# schematic.net
KiCad netlist of a schematic drawn in EasyEDA
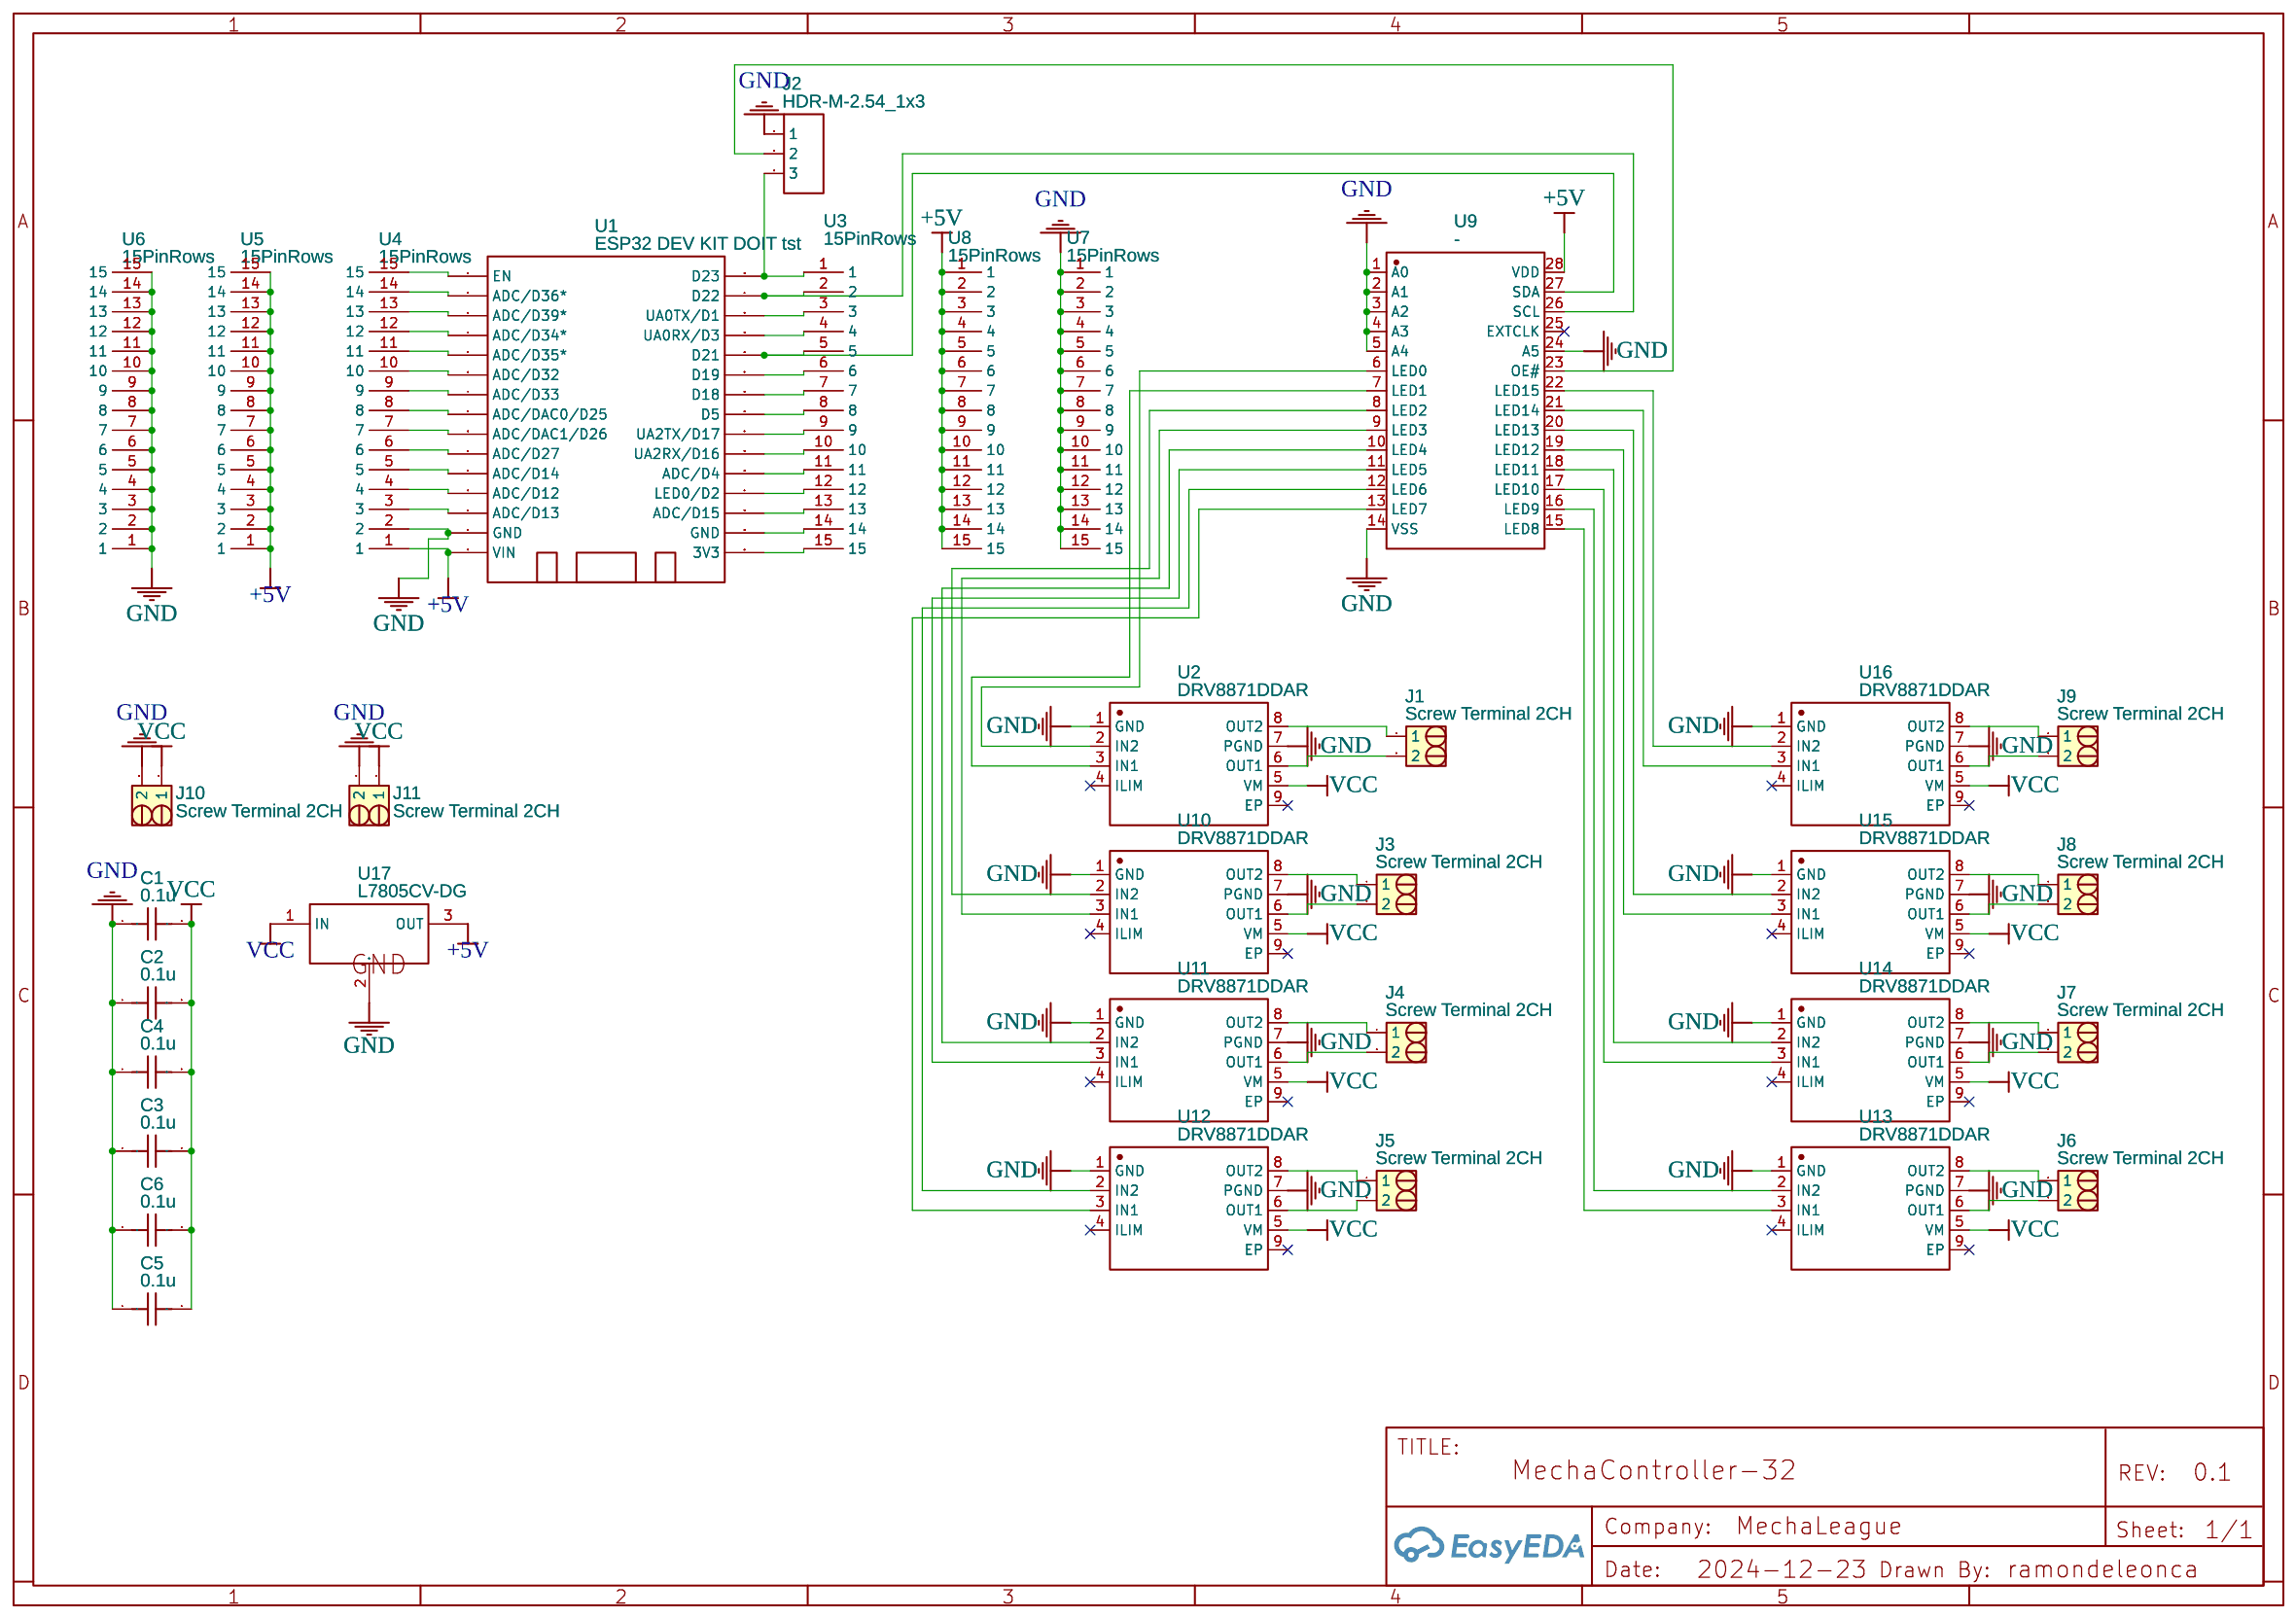
[diagram p0: schematic sheet]

(export (version "E")
  (design (tool "Eeschema 10.0.6"))
  (components
    (comp (ref "C1") (value "0.1u") (libsource (lib "") (part "C_0603_US")))
    (comp (ref "C2") (value "0.1u") (libsource (lib "") (part "C_0603_US")))
    (comp (ref "C3") (value "0.1u") (libsource (lib "") (part "C_0603_US")))
    (comp (ref "C4") (value "0.1u") (libsource (lib "") (part "C_0603_US")))
    (comp (ref "C5") (value "0.1u") (libsource (lib "") (part "C_0603_US")))
    (comp (ref "C6") (value "0.1u") (libsource (lib "") (part "C_0603_US")))
    (comp (ref "J1") (value "Screw Terminal 2CH") (libsource (lib "") (part "Screw Terminal 2CH")))
    (comp (ref "J2") (value "HDR-M-2.54_1x3") (libsource (lib "") (part "HDR-M-2.54_1x3")))
    (comp (ref "J3") (value "Screw Terminal 2CH") (libsource (lib "") (part "Screw Terminal 2CH")))
    (comp (ref "J4") (value "Screw Terminal 2CH") (libsource (lib "") (part "Screw Terminal 2CH")))
    (comp (ref "J5") (value "Screw Terminal 2CH") (libsource (lib "") (part "Screw Terminal 2CH")))
    (comp (ref "J6") (value "Screw Terminal 2CH") (libsource (lib "") (part "Screw Terminal 2CH")))
    (comp (ref "J7") (value "Screw Terminal 2CH") (libsource (lib "") (part "Screw Terminal 2CH")))
    (comp (ref "J8") (value "Screw Terminal 2CH") (libsource (lib "") (part "Screw Terminal 2CH")))
    (comp (ref "J9") (value "Screw Terminal 2CH") (libsource (lib "") (part "Screw Terminal 2CH")))
    (comp (ref "J10") (value "Screw Terminal 2CH") (libsource (lib "") (part "Screw Terminal 2CH_1")))
    (comp (ref "J11") (value "Screw Terminal 2CH") (libsource (lib "") (part "Screw Terminal 2CH_1")))
    (comp (ref "U1") (value "ESP32 DEV KIT DOIT tst") (libsource (lib "") (part "ESP32 DEV KIT DOIT tst")))
    (comp (ref "U2")
      (value "DRV8871DDAR")
      (fields (field (name "Manufacturer") "TI(德州仪器)"))
      (libsource (lib "") (part "DRV8871DDAR"))
    )
    (comp (ref "U3") (value "15PinRows") (libsource (lib "") (part "15PinRows_1")))
    (comp (ref "U4") (value "15PinRows") (libsource (lib "") (part "15PinRows")))
    (comp (ref "U5") (value "15PinRows") (libsource (lib "") (part "15PinRows")))
    (comp (ref "U6") (value "15PinRows") (libsource (lib "") (part "15PinRows")))
    (comp (ref "U7") (value "15PinRows") (libsource (lib "") (part "15PinRows_1")))
    (comp (ref "U8") (value "15PinRows") (libsource (lib "") (part "15PinRows_1")))
    (comp (ref "U9")
      (value "-")
      (fields (field (name "Manufacturer Part") "PCA9685PW,118") (field (name "Manufacturer") "NXP(恩智浦)"))
      (libsource (lib "") (part "PCA9685PW,118"))
    )
    (comp (ref "U10")
      (value "DRV8871DDAR")
      (fields (field (name "Manufacturer") "TI(德州仪器)"))
      (libsource (lib "") (part "DRV8871DDAR"))
    )
    (comp (ref "U11")
      (value "DRV8871DDAR")
      (fields (field (name "Manufacturer") "TI(德州仪器)"))
      (libsource (lib "") (part "DRV8871DDAR"))
    )
    (comp (ref "U12")
      (value "DRV8871DDAR")
      (fields (field (name "Manufacturer") "TI(德州仪器)"))
      (libsource (lib "") (part "DRV8871DDAR"))
    )
    (comp (ref "U13")
      (value "DRV8871DDAR")
      (fields (field (name "Manufacturer") "TI(德州仪器)"))
      (libsource (lib "") (part "DRV8871DDAR"))
    )
    (comp (ref "U14")
      (value "DRV8871DDAR")
      (fields (field (name "Manufacturer") "TI(德州仪器)"))
      (libsource (lib "") (part "DRV8871DDAR"))
    )
    (comp (ref "U15")
      (value "DRV8871DDAR")
      (fields (field (name "Manufacturer") "TI(德州仪器)"))
      (libsource (lib "") (part "DRV8871DDAR"))
    )
    (comp (ref "U16")
      (value "DRV8871DDAR")
      (fields (field (name "Manufacturer") "TI(德州仪器)"))
      (libsource (lib "") (part "DRV8871DDAR"))
    )
    (comp (ref "U17")
      (value "L7805CV-DG")
      (fields (field (name "Manufacturer") "ST(意法半导体)"))
      (libsource (lib "") (part "L7805CV-DG"))
    )
  )
  (nets
    (net (code "1") (name "+5V") (class "Default")
      (node (ref "U1") (pin "15") (pinfunction "VIN_15") (pintype "input"))
      (node (ref "U17") (pin "3") (pinfunction "OUT_3") (pintype "passive"))
      (node (ref "U4") (pin "1") (pinfunction "1_1") (pintype "unspecified"))
      (node (ref "U5") (pin "1") (pinfunction "1_1") (pintype "unspecified"))
      (node (ref "U5") (pin "10") (pinfunction "10_10") (pintype "unspecified"))
      (node (ref "U5") (pin "11") (pinfunction "11_11") (pintype "unspecified"))
      (node (ref "U5") (pin "12") (pinfunction "12_12") (pintype "unspecified"))
      (node (ref "U5") (pin "13") (pinfunction "13_13") (pintype "unspecified"))
      (node (ref "U5") (pin "14") (pinfunction "14_14") (pintype "unspecified"))
      (node (ref "U5") (pin "15") (pinfunction "15_15") (pintype "unspecified"))
      (node (ref "U5") (pin "2") (pinfunction "2_2") (pintype "unspecified"))
      (node (ref "U5") (pin "3") (pinfunction "3_3") (pintype "unspecified"))
      (node (ref "U5") (pin "4") (pinfunction "4_4") (pintype "unspecified"))
      (node (ref "U5") (pin "5") (pinfunction "5_5") (pintype "unspecified"))
      (node (ref "U5") (pin "6") (pinfunction "6_6") (pintype "unspecified"))
      (node (ref "U5") (pin "7") (pinfunction "7_7") (pintype "unspecified"))
      (node (ref "U5") (pin "8") (pinfunction "8_8") (pintype "unspecified"))
      (node (ref "U5") (pin "9") (pinfunction "9_9") (pintype "unspecified"))
      (node (ref "U8") (pin "1") (pinfunction "1_1") (pintype "unspecified"))
      (node (ref "U8") (pin "10") (pinfunction "10_10") (pintype "unspecified"))
      (node (ref "U8") (pin "11") (pinfunction "11_11") (pintype "unspecified"))
      (node (ref "U8") (pin "12") (pinfunction "12_12") (pintype "unspecified"))
      (node (ref "U8") (pin "13") (pinfunction "13_13") (pintype "unspecified"))
      (node (ref "U8") (pin "14") (pinfunction "14_14") (pintype "unspecified"))
      (node (ref "U8") (pin "15") (pinfunction "15_15") (pintype "unspecified"))
      (node (ref "U8") (pin "2") (pinfunction "2_2") (pintype "unspecified"))
      (node (ref "U8") (pin "3") (pinfunction "3_3") (pintype "unspecified"))
      (node (ref "U8") (pin "4") (pinfunction "4_4") (pintype "unspecified"))
      (node (ref "U8") (pin "5") (pinfunction "5_5") (pintype "unspecified"))
      (node (ref "U8") (pin "6") (pinfunction "6_6") (pintype "unspecified"))
      (node (ref "U8") (pin "7") (pinfunction "7_7") (pintype "unspecified"))
      (node (ref "U8") (pin "8") (pinfunction "8_8") (pintype "unspecified"))
      (node (ref "U8") (pin "9") (pinfunction "9_9") (pintype "unspecified"))
      (node (ref "U9") (pin "28") (pinfunction "VDD_28") (pintype "unspecified"))
    )
    (net (code "2") (name "GND") (class "Default")
      (node (ref "C1") (pin "1") (pinfunction "1_1") (pintype "unspecified"))
      (node (ref "C2") (pin "1") (pinfunction "1_1") (pintype "unspecified"))
      (node (ref "C3") (pin "1") (pinfunction "1_1") (pintype "unspecified"))
      (node (ref "C4") (pin "1") (pinfunction "1_1") (pintype "unspecified"))
      (node (ref "C5") (pin "1") (pinfunction "1_1") (pintype "unspecified"))
      (node (ref "C6") (pin "1") (pinfunction "1_1") (pintype "unspecified"))
      (node (ref "J10") (pin "2") (pinfunction "2_2") (pintype "unspecified"))
      (node (ref "J11") (pin "2") (pinfunction "2_2") (pintype "unspecified"))
      (node (ref "J2") (pin "1") (pinfunction "1_1") (pintype "input"))
      (node (ref "U1") (pin "14") (pinfunction "GND_14") (pintype "bidirectional"))
      (node (ref "U10") (pin "1") (pinfunction "GND_1") (pintype "unspecified"))
      (node (ref "U10") (pin "7") (pinfunction "PGND_7") (pintype "unspecified"))
      (node (ref "U11") (pin "1") (pinfunction "GND_1") (pintype "unspecified"))
      (node (ref "U11") (pin "7") (pinfunction "PGND_7") (pintype "unspecified"))
      (node (ref "U12") (pin "1") (pinfunction "GND_1") (pintype "unspecified"))
      (node (ref "U12") (pin "7") (pinfunction "PGND_7") (pintype "unspecified"))
      (node (ref "U13") (pin "1") (pinfunction "GND_1") (pintype "unspecified"))
      (node (ref "U13") (pin "7") (pinfunction "PGND_7") (pintype "unspecified"))
      (node (ref "U14") (pin "1") (pinfunction "GND_1") (pintype "unspecified"))
      (node (ref "U14") (pin "7") (pinfunction "PGND_7") (pintype "unspecified"))
      (node (ref "U15") (pin "1") (pinfunction "GND_1") (pintype "unspecified"))
      (node (ref "U15") (pin "7") (pinfunction "PGND_7") (pintype "unspecified"))
      (node (ref "U16") (pin "1") (pinfunction "GND_1") (pintype "unspecified"))
      (node (ref "U16") (pin "7") (pinfunction "PGND_7") (pintype "unspecified"))
      (node (ref "U17") (pin "2") (pinfunction "GND_2") (pintype "passive"))
      (node (ref "U2") (pin "1") (pinfunction "GND_1") (pintype "unspecified"))
      (node (ref "U2") (pin "7") (pinfunction "PGND_7") (pintype "unspecified"))
      (node (ref "U4") (pin "2") (pinfunction "2_2") (pintype "unspecified"))
      (node (ref "U6") (pin "1") (pinfunction "1_1") (pintype "unspecified"))
      (node (ref "U6") (pin "10") (pinfunction "10_10") (pintype "unspecified"))
      (node (ref "U6") (pin "11") (pinfunction "11_11") (pintype "unspecified"))
      (node (ref "U6") (pin "12") (pinfunction "12_12") (pintype "unspecified"))
      (node (ref "U6") (pin "13") (pinfunction "13_13") (pintype "unspecified"))
      (node (ref "U6") (pin "14") (pinfunction "14_14") (pintype "unspecified"))
      (node (ref "U6") (pin "15") (pinfunction "15_15") (pintype "unspecified"))
      (node (ref "U6") (pin "2") (pinfunction "2_2") (pintype "unspecified"))
      (node (ref "U6") (pin "3") (pinfunction "3_3") (pintype "unspecified"))
      (node (ref "U6") (pin "4") (pinfunction "4_4") (pintype "unspecified"))
      (node (ref "U6") (pin "5") (pinfunction "5_5") (pintype "unspecified"))
      (node (ref "U6") (pin "6") (pinfunction "6_6") (pintype "unspecified"))
      (node (ref "U6") (pin "7") (pinfunction "7_7") (pintype "unspecified"))
      (node (ref "U6") (pin "8") (pinfunction "8_8") (pintype "unspecified"))
      (node (ref "U6") (pin "9") (pinfunction "9_9") (pintype "unspecified"))
      (node (ref "U7") (pin "1") (pinfunction "1_1") (pintype "unspecified"))
      (node (ref "U7") (pin "10") (pinfunction "10_10") (pintype "unspecified"))
      (node (ref "U7") (pin "11") (pinfunction "11_11") (pintype "unspecified"))
      (node (ref "U7") (pin "12") (pinfunction "12_12") (pintype "unspecified"))
      (node (ref "U7") (pin "13") (pinfunction "13_13") (pintype "unspecified"))
      (node (ref "U7") (pin "14") (pinfunction "14_14") (pintype "unspecified"))
      (node (ref "U7") (pin "15") (pinfunction "15_15") (pintype "unspecified"))
      (node (ref "U7") (pin "2") (pinfunction "2_2") (pintype "unspecified"))
      (node (ref "U7") (pin "3") (pinfunction "3_3") (pintype "unspecified"))
      (node (ref "U7") (pin "4") (pinfunction "4_4") (pintype "unspecified"))
      (node (ref "U7") (pin "5") (pinfunction "5_5") (pintype "unspecified"))
      (node (ref "U7") (pin "6") (pinfunction "6_6") (pintype "unspecified"))
      (node (ref "U7") (pin "7") (pinfunction "7_7") (pintype "unspecified"))
      (node (ref "U7") (pin "8") (pinfunction "8_8") (pintype "unspecified"))
      (node (ref "U7") (pin "9") (pinfunction "9_9") (pintype "unspecified"))
      (node (ref "U9") (pin "1") (pinfunction "A0_1") (pintype "unspecified"))
      (node (ref "U9") (pin "14") (pinfunction "VSS_14") (pintype "unspecified"))
      (node (ref "U9") (pin "2") (pinfunction "A1_2") (pintype "unspecified"))
      (node (ref "U9") (pin "24") (pinfunction "A5_24") (pintype "unspecified"))
      (node (ref "U9") (pin "3") (pinfunction "A2_3") (pintype "unspecified"))
      (node (ref "U9") (pin "4") (pinfunction "A3_4") (pintype "unspecified"))
      (node (ref "U9") (pin "5") (pinfunction "A4_5") (pintype "unspecified"))
    )
    (net (code "3") (name "Net-(U1-3V3)") (class "Default")
      (node (ref "U1") (pin "30") (pinfunction "3V3_30") (pintype "bidirectional"))
      (node (ref "U3") (pin "15") (pinfunction "15_15") (pintype "unspecified"))
    )
    (net (code "4") (name "Net-(U1-ADC{slash}D4)") (class "Default")
      (node (ref "U1") (pin "26") (pinfunction "ADC/D4_26") (pintype "bidirectional"))
      (node (ref "U3") (pin "11") (pinfunction "11_11") (pintype "unspecified"))
    )
    (net (code "5") (name "Net-(U1-ADC{slash}D12)") (class "Default")
      (node (ref "U1") (pin "12") (pinfunction "ADC/D12_12") (pintype "bidirectional"))
      (node (ref "U4") (pin "4") (pinfunction "4_4") (pintype "unspecified"))
    )
    (net (code "6") (name "Net-(U1-ADC{slash}D13)") (class "Default")
      (node (ref "U1") (pin "13") (pinfunction "ADC/D13_13") (pintype "bidirectional"))
      (node (ref "U4") (pin "3") (pinfunction "3_3") (pintype "unspecified"))
    )
    (net (code "7") (name "Net-(U1-ADC{slash}D14)") (class "Default")
      (node (ref "U1") (pin "11") (pinfunction "ADC/D14_11") (pintype "bidirectional"))
      (node (ref "U4") (pin "5") (pinfunction "5_5") (pintype "unspecified"))
    )
    (net (code "8") (name "Net-(U1-ADC{slash}D15)") (class "Default")
      (node (ref "U1") (pin "28") (pinfunction "ADC/D15_28") (pintype "bidirectional"))
      (node (ref "U3") (pin "13") (pinfunction "13_13") (pintype "unspecified"))
    )
    (net (code "9") (name "Net-(U1-ADC{slash}D27)") (class "Default")
      (node (ref "U1") (pin "10") (pinfunction "ADC/D27_10") (pintype "bidirectional"))
      (node (ref "U4") (pin "6") (pinfunction "6_6") (pintype "unspecified"))
    )
    (net (code "10") (name "Net-(U1-ADC{slash}D32)") (class "Default")
      (node (ref "U1") (pin "6") (pinfunction "ADC/D32_6") (pintype "bidirectional"))
      (node (ref "U4") (pin "10") (pinfunction "10_10") (pintype "unspecified"))
    )
    (net (code "11") (name "Net-(U1-ADC{slash}D33)") (class "Default")
      (node (ref "U1") (pin "7") (pinfunction "ADC/D33_7") (pintype "bidirectional"))
      (node (ref "U4") (pin "9") (pinfunction "9_9") (pintype "unspecified"))
    )
    (net (code "12") (name "Net-(U1-ADC{slash}D34*)") (class "Default")
      (node (ref "U1") (pin "4") (pinfunction "ADC/D34*_4") (pintype "input"))
      (node (ref "U4") (pin "12") (pinfunction "12_12") (pintype "unspecified"))
    )
    (net (code "13") (name "Net-(U1-ADC{slash}D35*)") (class "Default")
      (node (ref "U1") (pin "5") (pinfunction "ADC/D35*_5") (pintype "input"))
      (node (ref "U4") (pin "11") (pinfunction "11_11") (pintype "unspecified"))
    )
    (net (code "14") (name "Net-(U1-ADC{slash}D36*)") (class "Default")
      (node (ref "U1") (pin "2") (pinfunction "ADC/D36*_2") (pintype "input"))
      (node (ref "U4") (pin "14") (pinfunction "14_14") (pintype "unspecified"))
    )
    (net (code "15") (name "Net-(U1-ADC{slash}D39*)") (class "Default")
      (node (ref "U1") (pin "3") (pinfunction "ADC/D39*_3") (pintype "input"))
      (node (ref "U4") (pin "13") (pinfunction "13_13") (pintype "unspecified"))
    )
    (net (code "16") (name "Net-(U1-ADC{slash}DAC0{slash}D25)") (class "Default")
      (node (ref "U1") (pin "8") (pinfunction "ADC/DAC0/D25_8") (pintype "bidirectional"))
      (node (ref "U4") (pin "8") (pinfunction "8_8") (pintype "unspecified"))
    )
    (net (code "17") (name "Net-(U1-ADC{slash}DAC1{slash}D26)") (class "Default")
      (node (ref "U1") (pin "9") (pinfunction "ADC/DAC1/D26_9") (pintype "bidirectional"))
      (node (ref "U4") (pin "7") (pinfunction "7_7") (pintype "unspecified"))
    )
    (net (code "18") (name "Net-(U1-D5)") (class "Default")
      (node (ref "U1") (pin "23") (pinfunction "D5_23") (pintype "bidirectional"))
      (node (ref "U3") (pin "8") (pinfunction "8_8") (pintype "unspecified"))
    )
    (net (code "19") (name "Net-(U1-D18)") (class "Default")
      (node (ref "U1") (pin "22") (pinfunction "D18_22") (pintype "bidirectional"))
      (node (ref "U3") (pin "7") (pinfunction "7_7") (pintype "unspecified"))
    )
    (net (code "20") (name "Net-(U1-D19)") (class "Default")
      (node (ref "U1") (pin "21") (pinfunction "D19_21") (pintype "bidirectional"))
      (node (ref "U3") (pin "6") (pinfunction "6_6") (pintype "unspecified"))
    )
    (net (code "21") (name "Net-(U1-D21)") (class "Default")
      (node (ref "U1") (pin "20") (pinfunction "D21_20") (pintype "bidirectional"))
      (node (ref "U3") (pin "5") (pinfunction "5_5") (pintype "unspecified"))
      (node (ref "U9") (pin "27") (pinfunction "SDA_27") (pintype "unspecified"))
    )
    (net (code "22") (name "Net-(U1-D22)") (class "Default")
      (node (ref "U1") (pin "17") (pinfunction "D22_17") (pintype "bidirectional"))
      (node (ref "U3") (pin "2") (pinfunction "2_2") (pintype "unspecified"))
      (node (ref "U9") (pin "26") (pinfunction "SCL_26") (pintype "unspecified"))
    )
    (net (code "23") (name "Net-(U1-D23)") (class "Default")
      (node (ref "J2") (pin "3") (pinfunction "3_3") (pintype "input"))
      (node (ref "U1") (pin "16") (pinfunction "D23_16") (pintype "bidirectional"))
      (node (ref "U3") (pin "1") (pinfunction "1_1") (pintype "unspecified"))
    )
    (net (code "24") (name "Net-(U1-EN)") (class "Default")
      (node (ref "U1") (pin "1") (pinfunction "EN_1") (pintype "bidirectional"))
      (node (ref "U4") (pin "15") (pinfunction "15_15") (pintype "unspecified"))
    )
    (net (code "25") (name "Net-(U1-GND-Pad29)") (class "Default")
      (node (ref "U1") (pin "29") (pinfunction "GND_29") (pintype "bidirectional"))
      (node (ref "U3") (pin "14") (pinfunction "14_14") (pintype "unspecified"))
    )
    (net (code "26") (name "Net-(U1-LED0{slash}D2)") (class "Default")
      (node (ref "U1") (pin "27") (pinfunction "LED0/D2_27") (pintype "bidirectional"))
      (node (ref "U3") (pin "12") (pinfunction "12_12") (pintype "unspecified"))
    )
    (net (code "27") (name "Net-(U1-UA0RX{slash}D3)") (class "Default")
      (node (ref "U1") (pin "19") (pinfunction "UA0RX/D3_19") (pintype "bidirectional"))
      (node (ref "U3") (pin "4") (pinfunction "4_4") (pintype "unspecified"))
    )
    (net (code "28") (name "Net-(U1-UA0TX{slash}D1)") (class "Default")
      (node (ref "U1") (pin "18") (pinfunction "UA0TX/D1_18") (pintype "bidirectional"))
      (node (ref "U3") (pin "3") (pinfunction "3_3") (pintype "unspecified"))
    )
    (net (code "29") (name "Net-(U1-UA2RX{slash}D16)") (class "Default")
      (node (ref "U1") (pin "25") (pinfunction "UA2RX/D16_25") (pintype "bidirectional"))
      (node (ref "U3") (pin "10") (pinfunction "10_10") (pintype "unspecified"))
    )
    (net (code "30") (name "Net-(U1-UA2TX{slash}D17)") (class "Default")
      (node (ref "U1") (pin "24") (pinfunction "UA2TX/D17_24") (pintype "bidirectional"))
      (node (ref "U3") (pin "9") (pinfunction "9_9") (pintype "unspecified"))
    )
    (net (code "31") (name "Net-(U2-IN1)") (class "Default")
      (node (ref "U2") (pin "3") (pinfunction "IN1_3") (pintype "unspecified"))
      (node (ref "U9") (pin "7") (pinfunction "LED1_7") (pintype "unspecified"))
    )
    (net (code "32") (name "Net-(U2-IN2)") (class "Default")
      (node (ref "U2") (pin "2") (pinfunction "IN2_2") (pintype "unspecified"))
      (node (ref "U9") (pin "6") (pinfunction "LED0_6") (pintype "unspecified"))
    )
    (net (code "33") (name "Net-(U2-OUT1)") (class "Default")
      (node (ref "J1") (pin "2") (pinfunction "2_2") (pintype "unspecified"))
      (node (ref "U2") (pin "6") (pinfunction "OUT1_6") (pintype "unspecified"))
    )
    (net (code "34") (name "Net-(U2-OUT2)") (class "Default")
      (node (ref "J1") (pin "1") (pinfunction "1_1") (pintype "unspecified"))
      (node (ref "U2") (pin "8") (pinfunction "OUT2_8") (pintype "unspecified"))
    )
    (net (code "35") (name "Net-(U9-OE#)") (class "Default")
      (node (ref "J2") (pin "2") (pinfunction "2_2") (pintype "input"))
      (node (ref "U9") (pin "23") (pinfunction "OE#_23") (pintype "unspecified"))
    )
    (net (code "36") (name "Net-(U10-IN1)") (class "Default")
      (node (ref "U10") (pin "3") (pinfunction "IN1_3") (pintype "unspecified"))
      (node (ref "U9") (pin "9") (pinfunction "LED3_9") (pintype "unspecified"))
    )
    (net (code "37") (name "Net-(U10-IN2)") (class "Default")
      (node (ref "U10") (pin "2") (pinfunction "IN2_2") (pintype "unspecified"))
      (node (ref "U9") (pin "8") (pinfunction "LED2_8") (pintype "unspecified"))
    )
    (net (code "38") (name "Net-(U10-OUT1)") (class "Default")
      (node (ref "J3") (pin "2") (pinfunction "2_2") (pintype "unspecified"))
      (node (ref "U10") (pin "6") (pinfunction "OUT1_6") (pintype "unspecified"))
    )
    (net (code "39") (name "Net-(U10-OUT2)") (class "Default")
      (node (ref "J3") (pin "1") (pinfunction "1_1") (pintype "unspecified"))
      (node (ref "U10") (pin "8") (pinfunction "OUT2_8") (pintype "unspecified"))
    )
    (net (code "40") (name "Net-(U11-IN1)") (class "Default")
      (node (ref "U11") (pin "3") (pinfunction "IN1_3") (pintype "unspecified"))
      (node (ref "U9") (pin "11") (pinfunction "LED5_11") (pintype "unspecified"))
    )
    (net (code "41") (name "Net-(U11-IN2)") (class "Default")
      (node (ref "U11") (pin "2") (pinfunction "IN2_2") (pintype "unspecified"))
      (node (ref "U9") (pin "10") (pinfunction "LED4_10") (pintype "unspecified"))
    )
    (net (code "42") (name "Net-(U11-OUT1)") (class "Default")
      (node (ref "J4") (pin "2") (pinfunction "2_2") (pintype "unspecified"))
      (node (ref "U11") (pin "6") (pinfunction "OUT1_6") (pintype "unspecified"))
    )
    (net (code "43") (name "Net-(U11-OUT2)") (class "Default")
      (node (ref "J4") (pin "1") (pinfunction "1_1") (pintype "unspecified"))
      (node (ref "U11") (pin "8") (pinfunction "OUT2_8") (pintype "unspecified"))
    )
    (net (code "44") (name "Net-(U12-IN1)") (class "Default")
      (node (ref "U12") (pin "3") (pinfunction "IN1_3") (pintype "unspecified"))
      (node (ref "U9") (pin "13") (pinfunction "LED7_13") (pintype "unspecified"))
    )
    (net (code "45") (name "Net-(U12-IN2)") (class "Default")
      (node (ref "U12") (pin "2") (pinfunction "IN2_2") (pintype "unspecified"))
      (node (ref "U9") (pin "12") (pinfunction "LED6_12") (pintype "unspecified"))
    )
    (net (code "46") (name "Net-(U12-OUT1)") (class "Default")
      (node (ref "J5") (pin "2") (pinfunction "2_2") (pintype "unspecified"))
      (node (ref "U12") (pin "6") (pinfunction "OUT1_6") (pintype "unspecified"))
    )
    (net (code "47") (name "Net-(U12-OUT2)") (class "Default")
      (node (ref "J5") (pin "1") (pinfunction "1_1") (pintype "unspecified"))
      (node (ref "U12") (pin "8") (pinfunction "OUT2_8") (pintype "unspecified"))
    )
    (net (code "48") (name "Net-(U13-IN1)") (class "Default")
      (node (ref "U13") (pin "3") (pinfunction "IN1_3") (pintype "unspecified"))
      (node (ref "U9") (pin "15") (pinfunction "LED8_15") (pintype "unspecified"))
    )
    (net (code "49") (name "Net-(U13-IN2)") (class "Default")
      (node (ref "U13") (pin "2") (pinfunction "IN2_2") (pintype "unspecified"))
      (node (ref "U9") (pin "16") (pinfunction "LED9_16") (pintype "unspecified"))
    )
    (net (code "50") (name "Net-(U13-OUT1)") (class "Default")
      (node (ref "J6") (pin "2") (pinfunction "2_2") (pintype "unspecified"))
      (node (ref "U13") (pin "6") (pinfunction "OUT1_6") (pintype "unspecified"))
    )
    (net (code "51") (name "Net-(U13-OUT2)") (class "Default")
      (node (ref "J6") (pin "1") (pinfunction "1_1") (pintype "unspecified"))
      (node (ref "U13") (pin "8") (pinfunction "OUT2_8") (pintype "unspecified"))
    )
    (net (code "52") (name "Net-(U14-IN1)") (class "Default")
      (node (ref "U14") (pin "3") (pinfunction "IN1_3") (pintype "unspecified"))
      (node (ref "U9") (pin "17") (pinfunction "LED10_17") (pintype "unspecified"))
    )
    (net (code "53") (name "Net-(U14-IN2)") (class "Default")
      (node (ref "U14") (pin "2") (pinfunction "IN2_2") (pintype "unspecified"))
      (node (ref "U9") (pin "18") (pinfunction "LED11_18") (pintype "unspecified"))
    )
    (net (code "54") (name "Net-(U14-OUT1)") (class "Default")
      (node (ref "J7") (pin "2") (pinfunction "2_2") (pintype "unspecified"))
      (node (ref "U14") (pin "6") (pinfunction "OUT1_6") (pintype "unspecified"))
    )
    (net (code "55") (name "Net-(U14-OUT2)") (class "Default")
      (node (ref "J7") (pin "1") (pinfunction "1_1") (pintype "unspecified"))
      (node (ref "U14") (pin "8") (pinfunction "OUT2_8") (pintype "unspecified"))
    )
    (net (code "56") (name "Net-(U15-IN1)") (class "Default")
      (node (ref "U15") (pin "3") (pinfunction "IN1_3") (pintype "unspecified"))
      (node (ref "U9") (pin "19") (pinfunction "LED12_19") (pintype "unspecified"))
    )
    (net (code "57") (name "Net-(U15-IN2)") (class "Default")
      (node (ref "U15") (pin "2") (pinfunction "IN2_2") (pintype "unspecified"))
      (node (ref "U9") (pin "20") (pinfunction "LED13_20") (pintype "unspecified"))
    )
    (net (code "58") (name "Net-(U15-OUT1)") (class "Default")
      (node (ref "J8") (pin "2") (pinfunction "2_2") (pintype "unspecified"))
      (node (ref "U15") (pin "6") (pinfunction "OUT1_6") (pintype "unspecified"))
    )
    (net (code "59") (name "Net-(U15-OUT2)") (class "Default")
      (node (ref "J8") (pin "1") (pinfunction "1_1") (pintype "unspecified"))
      (node (ref "U15") (pin "8") (pinfunction "OUT2_8") (pintype "unspecified"))
    )
    (net (code "60") (name "Net-(U16-IN1)") (class "Default")
      (node (ref "U16") (pin "3") (pinfunction "IN1_3") (pintype "unspecified"))
      (node (ref "U9") (pin "21") (pinfunction "LED14_21") (pintype "unspecified"))
    )
    (net (code "61") (name "Net-(U16-IN2)") (class "Default")
      (node (ref "U16") (pin "2") (pinfunction "IN2_2") (pintype "unspecified"))
      (node (ref "U9") (pin "22") (pinfunction "LED15_22") (pintype "unspecified"))
    )
    (net (code "62") (name "Net-(U16-OUT1)") (class "Default")
      (node (ref "J9") (pin "2") (pinfunction "2_2") (pintype "unspecified"))
      (node (ref "U16") (pin "6") (pinfunction "OUT1_6") (pintype "unspecified"))
    )
    (net (code "63") (name "Net-(U16-OUT2)") (class "Default")
      (node (ref "J9") (pin "1") (pinfunction "1_1") (pintype "unspecified"))
      (node (ref "U16") (pin "8") (pinfunction "OUT2_8") (pintype "unspecified"))
    )
    (net (code "64") (name "VCC") (class "Default")
      (node (ref "C1") (pin "2") (pinfunction "2_2") (pintype "unspecified"))
      (node (ref "C2") (pin "2") (pinfunction "2_2") (pintype "unspecified"))
      (node (ref "C3") (pin "2") (pinfunction "2_2") (pintype "unspecified"))
      (node (ref "C4") (pin "2") (pinfunction "2_2") (pintype "unspecified"))
      (node (ref "C5") (pin "2") (pinfunction "2_2") (pintype "unspecified"))
      (node (ref "C6") (pin "2") (pinfunction "2_2") (pintype "unspecified"))
      (node (ref "J10") (pin "1") (pinfunction "1_1") (pintype "unspecified"))
      (node (ref "J11") (pin "1") (pinfunction "1_1") (pintype "unspecified"))
      (node (ref "U10") (pin "5") (pinfunction "VM_5") (pintype "unspecified"))
      (node (ref "U11") (pin "5") (pinfunction "VM_5") (pintype "unspecified"))
      (node (ref "U12") (pin "5") (pinfunction "VM_5") (pintype "unspecified"))
      (node (ref "U13") (pin "5") (pinfunction "VM_5") (pintype "unspecified"))
      (node (ref "U14") (pin "5") (pinfunction "VM_5") (pintype "unspecified"))
      (node (ref "U15") (pin "5") (pinfunction "VM_5") (pintype "unspecified"))
      (node (ref "U16") (pin "5") (pinfunction "VM_5") (pintype "unspecified"))
      (node (ref "U17") (pin "1") (pinfunction "IN_1") (pintype "passive"))
      (node (ref "U2") (pin "5") (pinfunction "VM_5") (pintype "unspecified"))
    )
    (net (code "65") (name "unconnected-(U2-EP-Pad9)") (class "Default")
      (node (ref "U2") (pin "9") (pinfunction "EP_9") (pintype "unspecified+no_connect"))
    )
    (net (code "66") (name "unconnected-(U2-ILIM-Pad4)") (class "Default")
      (node (ref "U2") (pin "4") (pinfunction "ILIM_4") (pintype "unspecified+no_connect"))
    )
    (net (code "67") (name "unconnected-(U9-EXTCLK-Pad25)") (class "Default")
      (node (ref "U9") (pin "25") (pinfunction "EXTCLK_25") (pintype "unspecified+no_connect"))
    )
    (net (code "68") (name "unconnected-(U10-EP-Pad9)") (class "Default")
      (node (ref "U10") (pin "9") (pinfunction "EP_9") (pintype "unspecified+no_connect"))
    )
    (net (code "69") (name "unconnected-(U10-ILIM-Pad4)") (class "Default")
      (node (ref "U10") (pin "4") (pinfunction "ILIM_4") (pintype "unspecified+no_connect"))
    )
    (net (code "70") (name "unconnected-(U11-EP-Pad9)") (class "Default")
      (node (ref "U11") (pin "9") (pinfunction "EP_9") (pintype "unspecified+no_connect"))
    )
    (net (code "71") (name "unconnected-(U11-ILIM-Pad4)") (class "Default")
      (node (ref "U11") (pin "4") (pinfunction "ILIM_4") (pintype "unspecified+no_connect"))
    )
    (net (code "72") (name "unconnected-(U12-EP-Pad9)") (class "Default")
      (node (ref "U12") (pin "9") (pinfunction "EP_9") (pintype "unspecified+no_connect"))
    )
    (net (code "73") (name "unconnected-(U12-ILIM-Pad4)") (class "Default")
      (node (ref "U12") (pin "4") (pinfunction "ILIM_4") (pintype "unspecified+no_connect"))
    )
    (net (code "74") (name "unconnected-(U13-EP-Pad9)") (class "Default")
      (node (ref "U13") (pin "9") (pinfunction "EP_9") (pintype "unspecified+no_connect"))
    )
    (net (code "75") (name "unconnected-(U13-ILIM-Pad4)") (class "Default")
      (node (ref "U13") (pin "4") (pinfunction "ILIM_4") (pintype "unspecified+no_connect"))
    )
    (net (code "76") (name "unconnected-(U14-EP-Pad9)") (class "Default")
      (node (ref "U14") (pin "9") (pinfunction "EP_9") (pintype "unspecified+no_connect"))
    )
    (net (code "77") (name "unconnected-(U14-ILIM-Pad4)") (class "Default")
      (node (ref "U14") (pin "4") (pinfunction "ILIM_4") (pintype "unspecified+no_connect"))
    )
    (net (code "78") (name "unconnected-(U15-EP-Pad9)") (class "Default")
      (node (ref "U15") (pin "9") (pinfunction "EP_9") (pintype "unspecified+no_connect"))
    )
    (net (code "79") (name "unconnected-(U15-ILIM-Pad4)") (class "Default")
      (node (ref "U15") (pin "4") (pinfunction "ILIM_4") (pintype "unspecified+no_connect"))
    )
    (net (code "80") (name "unconnected-(U16-EP-Pad9)") (class "Default")
      (node (ref "U16") (pin "9") (pinfunction "EP_9") (pintype "unspecified+no_connect"))
    )
    (net (code "81") (name "unconnected-(U16-ILIM-Pad4)") (class "Default")
      (node (ref "U16") (pin "4") (pinfunction "ILIM_4") (pintype "unspecified+no_connect"))
    )
  )
)
